# ique_xbox_flex_r0.net
KiCad netlist of a schematic drawn in EasyEDA Pro
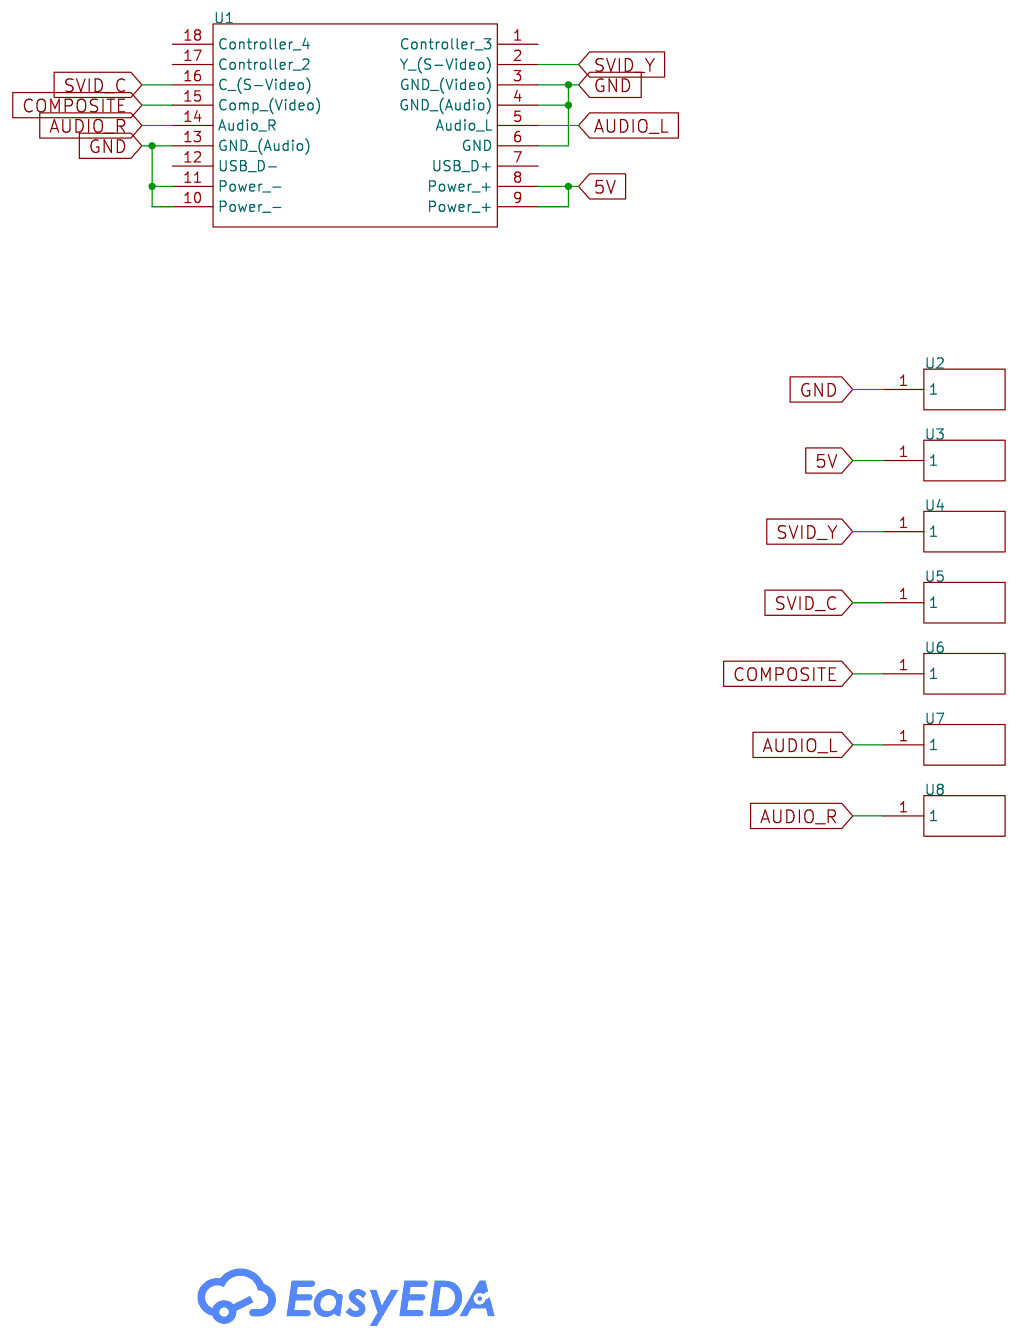
[diagram p0: schematic sheet]

(export (version "E")
  (design (tool "Eeschema 10.0.6"))
  (components
    (comp (ref "U1")
      (value "~")
      (footprint "easyedapro:iQue_Connector_Flex")
      (libsource (lib "easyedapro") (part "ique_connector_flex"))
    )
    (comp (ref "U2")
      (value "~")
      (footprint "easyedapro:sqpad_3mm")
      (libsource (lib "easyedapro") (part "sqpad_3mm"))
    )
    (comp (ref "U3")
      (value "~")
      (footprint "easyedapro:sqpad_3mm")
      (libsource (lib "easyedapro") (part "sqpad_3mm"))
    )
    (comp (ref "U4")
      (value "~")
      (footprint "easyedapro:sqpad_3mm")
      (libsource (lib "easyedapro") (part "sqpad_3mm"))
    )
    (comp (ref "U5")
      (value "~")
      (footprint "easyedapro:sqpad_3mm")
      (libsource (lib "easyedapro") (part "sqpad_3mm"))
    )
    (comp (ref "U6")
      (value "~")
      (footprint "easyedapro:sqpad_3mm")
      (libsource (lib "easyedapro") (part "sqpad_3mm"))
    )
    (comp (ref "U7")
      (value "~")
      (footprint "easyedapro:sqpad_3mm")
      (libsource (lib "easyedapro") (part "sqpad_3mm"))
    )
    (comp (ref "U8")
      (value "~")
      (footprint "easyedapro:sqpad_3mm")
      (libsource (lib "easyedapro") (part "sqpad_3mm"))
    )
  )
  (nets
    (net (code "1") (name "5V") (class "Default")
      (node (ref "U1") (pin "8") (pinfunction "Power_+_8") (pintype "input"))
      (node (ref "U1") (pin "9") (pinfunction "Power_+_9") (pintype "input"))
      (node (ref "U3") (pin "1") (pinfunction "1_1") (pintype "input"))
    )
    (net (code "2") (name "AUDIO_L") (class "Default")
      (node (ref "U1") (pin "5") (pinfunction "Audio_L_5") (pintype "input"))
      (node (ref "U7") (pin "1") (pinfunction "1_1") (pintype "input"))
    )
    (net (code "3") (name "AUDIO_R") (class "Default")
      (node (ref "U1") (pin "14") (pinfunction "Audio_R_14") (pintype "input"))
      (node (ref "U8") (pin "1") (pinfunction "1_1") (pintype "input"))
    )
    (net (code "4") (name "COMPOSITE") (class "Default")
      (node (ref "U1") (pin "15") (pinfunction "Comp_(Video)_15") (pintype "input"))
      (node (ref "U6") (pin "1") (pinfunction "1_1") (pintype "input"))
    )
    (net (code "5") (name "GND") (class "Default")
      (node (ref "U1") (pin "10") (pinfunction "Power_-_10") (pintype "input"))
      (node (ref "U1") (pin "11") (pinfunction "Power_-_11") (pintype "input"))
      (node (ref "U1") (pin "13") (pinfunction "GND_(Audio)_13") (pintype "input"))
      (node (ref "U1") (pin "3") (pinfunction "GND_(Video)_3") (pintype "input"))
      (node (ref "U1") (pin "4") (pinfunction "GND_(Audio)_4") (pintype "input"))
      (node (ref "U1") (pin "6") (pinfunction "GND_6") (pintype "input"))
      (node (ref "U2") (pin "1") (pinfunction "1_1") (pintype "input"))
    )
    (net (code "6") (name "SVID_C") (class "Default")
      (node (ref "U1") (pin "16") (pinfunction "C_(S-Video)_16") (pintype "input"))
      (node (ref "U5") (pin "1") (pinfunction "1_1") (pintype "input"))
    )
    (net (code "7") (name "SVID_Y") (class "Default")
      (node (ref "U1") (pin "2") (pinfunction "Y_(S-Video)_2") (pintype "input"))
      (node (ref "U4") (pin "1") (pinfunction "1_1") (pintype "input"))
    )
    (net (code "8") (name "unconnected-(U1-Controller_2-Pad17)") (class "Default")
      (node (ref "U1") (pin "17") (pinfunction "Controller_2_17") (pintype "input"))
    )
    (net (code "9") (name "unconnected-(U1-Controller_3-Pad1)") (class "Default")
      (node (ref "U1") (pin "1") (pinfunction "Controller_3_1") (pintype "input"))
    )
    (net (code "10") (name "unconnected-(U1-Controller_4-Pad18)") (class "Default")
      (node (ref "U1") (pin "18") (pinfunction "Controller_4_18") (pintype "input"))
    )
    (net (code "11") (name "unconnected-(U1-USB_D+-Pad7)") (class "Default")
      (node (ref "U1") (pin "7") (pinfunction "USB_D+_7") (pintype "input"))
    )
    (net (code "12") (name "unconnected-(U1-USB_D--Pad12)") (class "Default")
      (node (ref "U1") (pin "12") (pinfunction "USB_D-_12") (pintype "input"))
    )
  )
)
